# yeasu.net
KiCad netlist of a schematic drawn in EAGLE
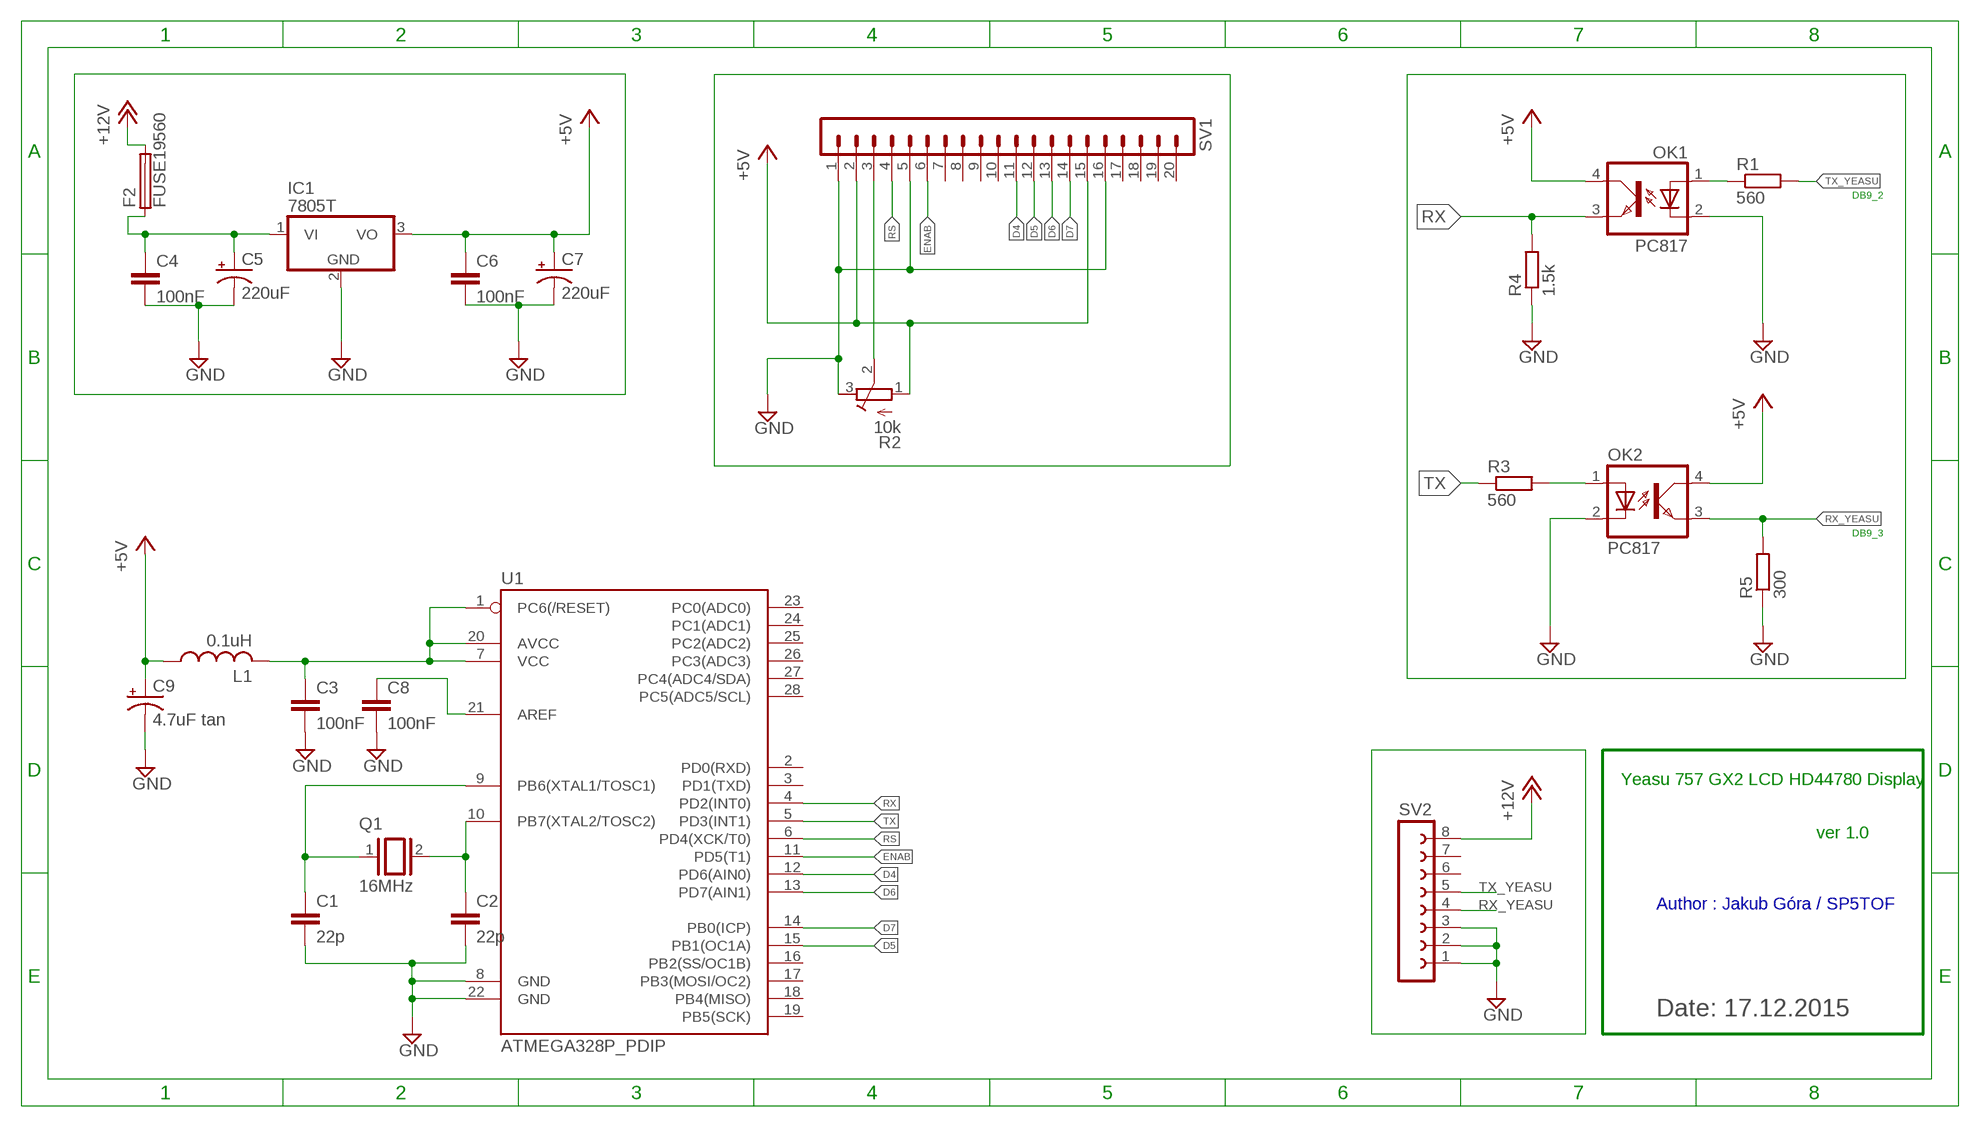
[diagram p0: schematic, sheet 1]

(export (version "E")
  (design (tool "Eeschema 10.0.6"))
  (components
    (comp (ref "C1")
      (value "22p")
      (footprint "eagle-import:C050-024X044")
      (libsource (lib "eagle-import") (part "C-EU050-024X044"))
    )
    (comp (ref "C2")
      (value "22p")
      (footprint "eagle-import:C050-024X044")
      (libsource (lib "eagle-import") (part "C-EU050-024X044"))
    )
    (comp (ref "C3")
      (value "100nF")
      (footprint "eagle-import:C050-024X044")
      (libsource (lib "eagle-import") (part "C-EU050-024X044"))
    )
    (comp (ref "C4")
      (value "100nF")
      (footprint "eagle-import:C050-024X044")
      (libsource (lib "eagle-import") (part "C-EU050-024X044"))
    )
    (comp (ref "C5")
      (value "220uF")
      (footprint "eagle-import:CPOL-RADIAL-1000UF-63V")
      (libsource (lib "eagle-import") (part "CAP_POLPTH3"))
    )
    (comp (ref "C6")
      (value "100nF")
      (footprint "eagle-import:C050-024X044")
      (libsource (lib "eagle-import") (part "C-EU050-024X044"))
    )
    (comp (ref "C7")
      (value "220uF")
      (footprint "eagle-import:CPOL-RADIAL-1000UF-63V")
      (libsource (lib "eagle-import") (part "CAP_POLPTH3"))
    )
    (comp (ref "C8")
      (value "100nF")
      (footprint "eagle-import:C050-024X044")
      (libsource (lib "eagle-import") (part "C-EU050-024X044"))
    )
    (comp (ref "C9")
      (value "4.7uF tan")
      (footprint "eagle-import:E2,5-6E")
      (libsource (lib "eagle-import") (part "CPOL-USE2,5-6E"))
    )
    (comp (ref "F2")
      (value "FUSE19560")
      (footprint "eagle-import:19560")
      (fields (field (name "MPN") "56000001009"))
      (libsource (lib "eagle-import") (part "FUSE19560"))
    )
    (comp (ref "IC1")
      (value "7805T")
      (footprint "eagle-import:TO220H")
      (libsource (lib "eagle-import") (part "78T05"))
    )
    (comp (ref "L1")
      (value "0.1uH")
      (footprint "eagle-import:0207_7")
      (libsource (lib "eagle-import") (part "L-US0207/7"))
    )
    (comp (ref "OK1")
      (value "PC817")
      (footprint "eagle-import:DIL04")
      (fields (field (name "MPN") "PC817X4J000F"))
      (libsource (lib "eagle-import") (part "PC817"))
    )
    (comp (ref "OK2")
      (value "PC817")
      (footprint "eagle-import:DIL04")
      (fields (field (name "MPN") "PC817X4J000F"))
      (libsource (lib "eagle-import") (part "PC817"))
    )
    (comp (ref "Q1")
      (value "16MHz")
      (footprint "eagle-import:QS")
      (libsource (lib "eagle-import") (part "XTAL/S"))
    )
    (comp (ref "R1")
      (value "560")
      (footprint "eagle-import:0207_10")
      (libsource (lib "eagle-import") (part "R-EU_0207/10"))
    )
    (comp (ref "R2")
      (value "10k")
      (footprint "eagle-import:RTRIM3339P")
      (libsource (lib "eagle-import") (part "R-TRIMM3339P"))
    )
    (comp (ref "R3")
      (value "560")
      (footprint "eagle-import:0207_10")
      (libsource (lib "eagle-import") (part "R-EU_0207/10"))
    )
    (comp (ref "R4")
      (value "1.5k")
      (footprint "eagle-import:0207_10")
      (libsource (lib "eagle-import") (part "R-EU_0207/10"))
    )
    (comp (ref "R5")
      (value "300")
      (footprint "eagle-import:0207_10")
      (libsource (lib "eagle-import") (part "R-EU_0207/10"))
    )
    (comp (ref "SV1")
      (value "MA20-1")
      (footprint "eagle-import:MA20-1")
      (libsource (lib "eagle-import") (part "MA20-1"))
    )
    (comp (ref "SV2")
      (value "FE08-1")
      (footprint "eagle-import:FE08")
      (libsource (lib "eagle-import") (part "FE08-1"))
    )
    (comp (ref "U1")
      (value "ATMEGA328P_PDIP")
      (footprint "eagle-import:DIL28-3")
      (libsource (lib "eagle-import") (part "ATMEGA328P_PDIP"))
    )
  )
  (nets
    (net (code "1") (name "+5V") (class "Default")
      (node (ref "C6") (pin "1") (pinfunction "1_1") (pintype "passive"))
      (node (ref "C7") (pin "1") (pinfunction "+_1") (pintype "passive"))
      (node (ref "C9") (pin "+") (pinfunction "+_+") (pintype "passive"))
      (node (ref "IC1") (pin "3") (pinfunction "VO_3") (pintype "passive"))
      (node (ref "L1") (pin "1") (pinfunction "1_1") (pintype "passive"))
      (node (ref "OK1") (pin "4") (pinfunction "COL_4") (pintype "passive"))
      (node (ref "OK2") (pin "4") (pinfunction "COL_4") (pintype "passive"))
      (node (ref "R2") (pin "1") (pinfunction "E_1") (pintype "passive"))
      (node (ref "SV1") (pin "15") (pinfunction "15_15") (pintype "passive"))
      (node (ref "SV1") (pin "2") (pinfunction "2_2") (pintype "passive"))
    )
    (net (code "2") (name "+12V") (class "Default")
      (node (ref "F2") (pin "2") (pinfunction "2_2") (pintype "passive"))
      (node (ref "SV2") (pin "8") (pinfunction "8_8") (pintype "passive"))
    )
    (net (code "3") (name "D4") (class "Default")
      (node (ref "SV1") (pin "11") (pinfunction "11_11") (pintype "passive"))
      (node (ref "U1") (pin "12") (pinfunction "PD6(AIN0)_12") (pintype "bidirectional"))
    )
    (net (code "4") (name "D5") (class "Default")
      (node (ref "SV1") (pin "12") (pinfunction "12_12") (pintype "passive"))
      (node (ref "U1") (pin "15") (pinfunction "PB1(OC1A)_15") (pintype "bidirectional"))
    )
    (net (code "5") (name "D6") (class "Default")
      (node (ref "SV1") (pin "13") (pinfunction "13_13") (pintype "passive"))
      (node (ref "U1") (pin "13") (pinfunction "PD7(AIN1)_13") (pintype "bidirectional"))
    )
    (net (code "6") (name "D7") (class "Default")
      (node (ref "SV1") (pin "14") (pinfunction "14_14") (pintype "passive"))
      (node (ref "U1") (pin "14") (pinfunction "PB0(ICP)_14") (pintype "bidirectional"))
    )
    (net (code "7") (name "ENAB") (class "Default")
      (node (ref "SV1") (pin "6") (pinfunction "6_6") (pintype "passive"))
      (node (ref "U1") (pin "11") (pinfunction "PD5(T1)_11") (pintype "bidirectional"))
    )
    (net (code "8") (name "GND") (class "Default")
      (node (ref "C1") (pin "2") (pinfunction "2_2") (pintype "passive"))
      (node (ref "C2") (pin "2") (pinfunction "2_2") (pintype "passive"))
      (node (ref "C3") (pin "2") (pinfunction "2_2") (pintype "passive"))
      (node (ref "C4") (pin "2") (pinfunction "2_2") (pintype "passive"))
      (node (ref "C5") (pin "2") (pinfunction "-_2") (pintype "passive"))
      (node (ref "C6") (pin "2") (pinfunction "2_2") (pintype "passive"))
      (node (ref "C7") (pin "2") (pinfunction "-_2") (pintype "passive"))
      (node (ref "C8") (pin "2") (pinfunction "2_2") (pintype "passive"))
      (node (ref "C9") (pin "-") (pinfunction "-_-") (pintype "passive"))
      (node (ref "IC1") (pin "2") (pinfunction "GND_2") (pintype "passive"))
      (node (ref "OK1") (pin "2") (pinfunction "C_2") (pintype "passive"))
      (node (ref "OK2") (pin "2") (pinfunction "C_2") (pintype "passive"))
      (node (ref "R2") (pin "3") (pinfunction "A_3") (pintype "passive"))
      (node (ref "R4") (pin "1") (pinfunction "1_1") (pintype "passive"))
      (node (ref "R5") (pin "1") (pinfunction "1_1") (pintype "passive"))
      (node (ref "SV1") (pin "1") (pinfunction "1_1") (pintype "passive"))
      (node (ref "SV1") (pin "16") (pinfunction "16_16") (pintype "passive"))
      (node (ref "SV1") (pin "5") (pinfunction "5_5") (pintype "passive"))
      (node (ref "SV2") (pin "1") (pinfunction "1_1") (pintype "passive"))
      (node (ref "SV2") (pin "2") (pinfunction "2_2") (pintype "passive"))
      (node (ref "SV2") (pin "3") (pinfunction "3_3") (pintype "passive"))
      (node (ref "U1") (pin "22") (pinfunction "GND_22") (pintype "bidirectional"))
      (node (ref "U1") (pin "8") (pinfunction "GND_8") (pintype "bidirectional"))
    )
    (net (code "9") (name "Net-(C5-+)") (class "Default")
      (node (ref "C4") (pin "1") (pinfunction "1_1") (pintype "passive"))
      (node (ref "C5") (pin "1") (pinfunction "+_1") (pintype "passive"))
      (node (ref "F2") (pin "1") (pinfunction "1_1") (pintype "passive"))
      (node (ref "IC1") (pin "1") (pinfunction "VI_1") (pintype "input"))
    )
    (net (code "10") (name "Net-(OK1-A)") (class "Default")
      (node (ref "OK1") (pin "1") (pinfunction "A_1") (pintype "passive"))
      (node (ref "R1") (pin "1") (pinfunction "1_1") (pintype "passive"))
    )
    (net (code "11") (name "Net-(OK2-A)") (class "Default")
      (node (ref "OK2") (pin "1") (pinfunction "A_1") (pintype "passive"))
      (node (ref "R3") (pin "2") (pinfunction "2_2") (pintype "passive"))
    )
    (net (code "12") (name "Net-(R2-S)") (class "Default")
      (node (ref "R2") (pin "2") (pinfunction "S_2") (pintype "passive"))
      (node (ref "SV1") (pin "3") (pinfunction "3_3") (pintype "passive"))
    )
    (net (code "13") (name "Net-(U1-AREF)") (class "Default")
      (node (ref "C8") (pin "1") (pinfunction "1_1") (pintype "passive"))
      (node (ref "U1") (pin "21") (pinfunction "AREF_21") (pintype "bidirectional"))
    )
    (net (code "14") (name "Net-(U1-AVCC)") (class "Default")
      (node (ref "C3") (pin "1") (pinfunction "1_1") (pintype "passive"))
      (node (ref "L1") (pin "2") (pinfunction "2_2") (pintype "passive"))
      (node (ref "U1") (pin "1") (pinfunction "PC6(/RESET)_1") (pintype "bidirectional"))
      (node (ref "U1") (pin "20") (pinfunction "AVCC_20") (pintype "bidirectional"))
      (node (ref "U1") (pin "7") (pinfunction "VCC_7") (pintype "bidirectional"))
    )
    (net (code "15") (name "Net-(U1-PB6(XTAL1{slash}TOSC1))") (class "Default")
      (node (ref "C1") (pin "1") (pinfunction "1_1") (pintype "passive"))
      (node (ref "Q1") (pin "1") (pinfunction "1_1") (pintype "passive"))
      (node (ref "U1") (pin "9") (pinfunction "PB6(XTAL1/TOSC1)_9") (pintype "bidirectional"))
    )
    (net (code "16") (name "Net-(U1-PB7(XTAL2{slash}TOSC2))") (class "Default")
      (node (ref "C2") (pin "1") (pinfunction "1_1") (pintype "passive"))
      (node (ref "Q1") (pin "2") (pinfunction "2_2") (pintype "passive"))
      (node (ref "U1") (pin "10") (pinfunction "PB7(XTAL2/TOSC2)_10") (pintype "bidirectional"))
    )
    (net (code "17") (name "RS") (class "Default")
      (node (ref "SV1") (pin "4") (pinfunction "4_4") (pintype "passive"))
      (node (ref "U1") (pin "6") (pinfunction "PD4(XCK/T0)_6") (pintype "bidirectional"))
    )
    (net (code "18") (name "RX") (class "Default")
      (node (ref "OK1") (pin "3") (pinfunction "EMIT_3") (pintype "passive"))
      (node (ref "R4") (pin "2") (pinfunction "2_2") (pintype "passive"))
      (node (ref "U1") (pin "4") (pinfunction "PD2(INT0)_4") (pintype "bidirectional"))
    )
    (net (code "19") (name "RX_YEASU") (class "Default")
      (node (ref "OK2") (pin "3") (pinfunction "EMIT_3") (pintype "passive"))
      (node (ref "R5") (pin "2") (pinfunction "2_2") (pintype "passive"))
      (node (ref "SV2") (pin "4") (pinfunction "4_4") (pintype "passive"))
    )
    (net (code "20") (name "TX") (class "Default")
      (node (ref "R3") (pin "1") (pinfunction "1_1") (pintype "passive"))
      (node (ref "U1") (pin "5") (pinfunction "PD3(INT1)_5") (pintype "bidirectional"))
    )
    (net (code "21") (name "TX_YEASU") (class "Default")
      (node (ref "R1") (pin "2") (pinfunction "2_2") (pintype "passive"))
      (node (ref "SV2") (pin "5") (pinfunction "5_5") (pintype "passive"))
    )
    (net (code "22") (name "unconnected-(SV1-Pad7)") (class "Default")
      (node (ref "SV1") (pin "7") (pinfunction "7_7") (pintype "passive"))
    )
    (net (code "23") (name "unconnected-(SV1-Pad8)") (class "Default")
      (node (ref "SV1") (pin "8") (pinfunction "8_8") (pintype "passive"))
    )
    (net (code "24") (name "unconnected-(SV1-Pad9)") (class "Default")
      (node (ref "SV1") (pin "9") (pinfunction "9_9") (pintype "passive"))
    )
    (net (code "25") (name "unconnected-(SV1-Pad10)") (class "Default")
      (node (ref "SV1") (pin "10") (pinfunction "10_10") (pintype "passive"))
    )
    (net (code "26") (name "unconnected-(SV1-Pad17)") (class "Default")
      (node (ref "SV1") (pin "17") (pinfunction "17_17") (pintype "passive"))
    )
    (net (code "27") (name "unconnected-(SV1-Pad18)") (class "Default")
      (node (ref "SV1") (pin "18") (pinfunction "18_18") (pintype "passive"))
    )
    (net (code "28") (name "unconnected-(SV1-Pad19)") (class "Default")
      (node (ref "SV1") (pin "19") (pinfunction "19_19") (pintype "passive"))
    )
    (net (code "29") (name "unconnected-(SV1-Pad20)") (class "Default")
      (node (ref "SV1") (pin "20") (pinfunction "20_20") (pintype "passive"))
    )
    (net (code "30") (name "unconnected-(SV2-Pad6)") (class "Default")
      (node (ref "SV2") (pin "6") (pinfunction "6_6") (pintype "passive"))
    )
    (net (code "31") (name "unconnected-(SV2-Pad7)") (class "Default")
      (node (ref "SV2") (pin "7") (pinfunction "7_7") (pintype "passive"))
    )
    (net (code "32") (name "unconnected-(U1-PB2(SS{slash}OC1B)-Pad16)") (class "Default")
      (node (ref "U1") (pin "16") (pinfunction "PB2(SS/OC1B)_16") (pintype "bidirectional"))
    )
    (net (code "33") (name "unconnected-(U1-PB3(MOSI{slash}OC2)-Pad17)") (class "Default")
      (node (ref "U1") (pin "17") (pinfunction "PB3(MOSI/OC2)_17") (pintype "bidirectional"))
    )
    (net (code "34") (name "unconnected-(U1-PB4(MISO)-Pad18)") (class "Default")
      (node (ref "U1") (pin "18") (pinfunction "PB4(MISO)_18") (pintype "bidirectional"))
    )
    (net (code "35") (name "unconnected-(U1-PB5(SCK)-Pad19)") (class "Default")
      (node (ref "U1") (pin "19") (pinfunction "PB5(SCK)_19") (pintype "bidirectional"))
    )
    (net (code "36") (name "unconnected-(U1-PC0(ADC0)-Pad23)") (class "Default")
      (node (ref "U1") (pin "23") (pinfunction "PC0(ADC0)_23") (pintype "bidirectional"))
    )
    (net (code "37") (name "unconnected-(U1-PC1(ADC1)-Pad24)") (class "Default")
      (node (ref "U1") (pin "24") (pinfunction "PC1(ADC1)_24") (pintype "bidirectional"))
    )
    (net (code "38") (name "unconnected-(U1-PC2(ADC2)-Pad25)") (class "Default")
      (node (ref "U1") (pin "25") (pinfunction "PC2(ADC2)_25") (pintype "bidirectional"))
    )
    (net (code "39") (name "unconnected-(U1-PC3(ADC3)-Pad26)") (class "Default")
      (node (ref "U1") (pin "26") (pinfunction "PC3(ADC3)_26") (pintype "bidirectional"))
    )
    (net (code "40") (name "unconnected-(U1-PC4(ADC4{slash}SDA)-Pad27)") (class "Default")
      (node (ref "U1") (pin "27") (pinfunction "PC4(ADC4/SDA)_27") (pintype "bidirectional"))
    )
    (net (code "41") (name "unconnected-(U1-PC5(ADC5{slash}SCL)-Pad28)") (class "Default")
      (node (ref "U1") (pin "28") (pinfunction "PC5(ADC5/SCL)_28") (pintype "bidirectional"))
    )
    (net (code "42") (name "unconnected-(U1-PD0(RXD)-Pad2)") (class "Default")
      (node (ref "U1") (pin "2") (pinfunction "PD0(RXD)_2") (pintype "bidirectional"))
    )
    (net (code "43") (name "unconnected-(U1-PD1(TXD)-Pad3)") (class "Default")
      (node (ref "U1") (pin "3") (pinfunction "PD1(TXD)_3") (pintype "bidirectional"))
    )
  )
)
